# DIGITAL_IOs.net
KiCad netlist of a schematic drawn in Altium Designer
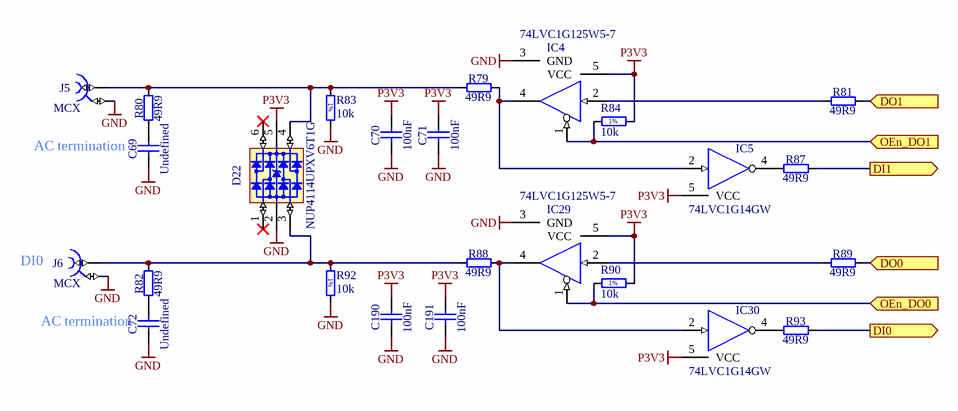
[diagram p0: DIGITAL_IOs.SchDoc]

(export (version "E")
  (design (tool "Eeschema 10.0.6"))
  (components
    (comp (ref "C69")
      (value "Undefined")
      (footprint "CAPC1608X90N")
      (description "Non-polarised capacitor")
      (fields (field (name "PART NUMBER") "CC0603_NO-VALUE") (field (name "AUTHOR") "CERN DEM MR"))
      (libsource (lib "Capacitors") (part "Capacitor - non polarized"))
    )
    (comp (ref "C70")
      (value "100nF")
      (footprint "CAPC1005X55N")
      (description "Non-polarised capacitor")
      (fields
        (field (name "PART NUMBER") "CC0402_100NF_16V_10%_X7R")
        (field (name "VOLTAGE") "16V")
        (field (name "AUTHOR") "CERN DEM JLC")
      )
      (libsource (lib "Capacitors") (part "Capacitor - non polarized"))
    )
    (comp (ref "C71")
      (value "100nF")
      (footprint "CAPC1005X55N")
      (description "Non-polarised capacitor")
      (fields
        (field (name "PART NUMBER") "CC0402_100NF_16V_10%_X7R")
        (field (name "VOLTAGE") "16V")
        (field (name "AUTHOR") "CERN DEM JLC")
      )
      (libsource (lib "Capacitors") (part "Capacitor - non polarized"))
    )
    (comp (ref "C72")
      (value "Undefined")
      (footprint "CAPC1608X90N")
      (description "Non-polarised capacitor")
      (fields (field (name "PART NUMBER") "CC0603_NO-VALUE") (field (name "AUTHOR") "CERN DEM MR"))
      (libsource (lib "Capacitors") (part "Capacitor - non polarized"))
    )
    (comp (ref "C190")
      (value "100nF")
      (footprint "CAPC1005X55N")
      (description "Non-polarised capacitor")
      (fields
        (field (name "PART NUMBER") "CC0402_100NF_16V_10%_X7R")
        (field (name "VOLTAGE") "16V")
        (field (name "AUTHOR") "CERN DEM JLC")
      )
      (libsource (lib "Capacitors") (part "Capacitor - non polarized"))
    )
    (comp (ref "C191")
      (value "100nF")
      (footprint "CAPC1005X55N")
      (description "Non-polarised capacitor")
      (fields
        (field (name "PART NUMBER") "CC0402_100NF_16V_10%_X7R")
        (field (name "VOLTAGE") "16V")
        (field (name "AUTHOR") "CERN DEM JLC")
      )
      (libsource (lib "Capacitors") (part "Capacitor - non polarized"))
    )
    (comp (ref "D22")
      (value "NUP4114UPXV6T1G")
      (footprint "SOTFL50P160X60-6N")
      (fields
        (field (name "VOLTAGE") "5.5V")
        (field (name "MANUFACTURER") "ON SEMICONDUCTOR")
        (field (name "AUTHOR") "CERN DEM JLC")
      )
      (libsource (lib "ICs And Semiconductors") (part "NUP4114"))
    )
    (comp (ref "IC4")
      (value "74LVC1G125W5-7")
      (footprint "SOT95P280X145-5N")
      (description "Single Bus Buffer Gate With 3-State Output")
      (fields (field (name "MANUFACTURER") "DIODES") (field (name "AUTHOR") "GK"))
      (libsource (lib "ICS-logic") (part "74LVC1G125W5-7"))
    )
    (comp (ref "IC5")
      (value "74LVC1G14GW")
      (footprint "SOT65P212X110-5N")
      (description "Single Schmitt-Trigger Inverter")
      (fields (field (name "MANUFACTURER") "NXP SEMICONDUCTORS") (field (name "AUTHOR") "CERN DEM JLC"))
      (libsource (lib "ICs And Semiconductors") (part "741G14"))
    )
    (comp (ref "IC29")
      (value "74LVC1G125W5-7")
      (footprint "SOT95P280X145-5N")
      (description "Single Bus Buffer Gate With 3-State Output")
      (fields (field (name "MANUFACTURER") "DIODES") (field (name "AUTHOR") "GK"))
      (libsource (lib "ICS-logic") (part "74LVC1G125W5-7"))
    )
    (comp (ref "IC30")
      (value "74LVC1G14GW")
      (footprint "SOT65P212X110-5N")
      (description "Single Schmitt-Trigger Inverter")
      (fields (field (name "MANUFACTURER") "NXP SEMICONDUCTORS") (field (name "AUTHOR") "CERN DEM JLC"))
      (libsource (lib "ICs And Semiconductors") (part "741G14"))
    )
    (comp (ref "J5")
      (value "MCX")
      (footprint "AMPHENOL_919-383J-51A")
      (fields
        (field (name "PART NUMBER") "AMPHENOL_919-383J-51A")
        (field (name "MANUFACTURER") "AMPHENOL")
        (field (name "MANUFACTURER PART NUMBER") "919-383J-51A")
        (field (name "AUTHOR") "CERN DEM BC")
      )
      (libsource (lib "Connectors") (part "Coax_1Female_1Shield"))
    )
    (comp (ref "J6")
      (value "MCX")
      (footprint "AMPHENOL_919-383J-51A")
      (fields
        (field (name "PART NUMBER") "AMPHENOL_919-383J-51A")
        (field (name "MANUFACTURER") "AMPHENOL")
        (field (name "MANUFACTURER PART NUMBER") "919-383J-51A")
        (field (name "AUTHOR") "CERN DEM BC")
      )
      (libsource (lib "Connectors") (part "Coax_1Female_1Shield"))
    )
    (comp (ref "R79")
      (value "49R9")
      (footprint "RESC1005X40N")
      (description "Resistor - 1%")
      (fields
        (field (name "PART NUMBER") "R0402_49R9_1%_0.0625W_100PPM")
        (field (name "POWER") "0.0625W")
        (field (name "AUTHOR") "CERN DEM JLC")
      )
      (libsource (lib "Resistors") (part "Resistor - 1%"))
    )
    (comp (ref "R80")
      (value "49R9")
      (footprint "RESC1005X40N")
      (description "Resistor - 1%")
      (fields
        (field (name "PART NUMBER") "R0402_49R9_1%_0.0625W_100PPM")
        (field (name "POWER") "0.0625W")
        (field (name "AUTHOR") "CERN DEM JLC")
      )
      (libsource (lib "Resistors") (part "Resistor - 1%"))
    )
    (comp (ref "R81")
      (value "49R9")
      (footprint "RESC1005X40N")
      (description "Resistor - 1%")
      (fields
        (field (name "PART NUMBER") "R0402_49R9_1%_0.0625W_100PPM")
        (field (name "POWER") "0.0625W")
        (field (name "AUTHOR") "CERN DEM JLC")
      )
      (libsource (lib "Resistors") (part "Resistor - 1%"))
    )
    (comp (ref "R82")
      (value "49R9")
      (footprint "RESC1005X40N")
      (description "Resistor - 1%")
      (fields
        (field (name "PART NUMBER") "R0402_49R9_1%_0.0625W_100PPM")
        (field (name "POWER") "0.0625W")
        (field (name "AUTHOR") "CERN DEM JLC")
      )
      (libsource (lib "Resistors") (part "Resistor - 1%"))
    )
    (comp (ref "R83")
      (value "10k")
      (footprint "RESC1005X40N")
      (description "Resistor - 1%")
      (fields
        (field (name "PART NUMBER") "R0402_10K_1%_0.0625W_100PPM")
        (field (name "POWER") "0.0625W")
        (field (name "AUTHOR") "CERN DEM JLC")
      )
      (libsource (lib "Resistors") (part "Resistor - 1%"))
    )
    (comp (ref "R84")
      (value "10k")
      (footprint "RESC1005X40N")
      (description "Resistor - 1%")
      (fields
        (field (name "PART NUMBER") "R0402_10K_1%_0.0625W_100PPM")
        (field (name "POWER") "0.0625W")
        (field (name "AUTHOR") "CERN DEM JLC")
      )
      (libsource (lib "Resistors") (part "Resistor - 1%"))
    )
    (comp (ref "R87")
      (value "49R9")
      (footprint "RESC1005X40N")
      (description "Resistor - 1%")
      (fields
        (field (name "PART NUMBER") "R0402_49R9_1%_0.0625W_100PPM")
        (field (name "POWER") "0.0625W")
        (field (name "AUTHOR") "CERN DEM JLC")
      )
      (libsource (lib "Resistors") (part "Resistor - 1%"))
    )
    (comp (ref "R88")
      (value "49R9")
      (footprint "RESC1005X40N")
      (description "Resistor - 1%")
      (fields
        (field (name "PART NUMBER") "R0402_49R9_1%_0.0625W_100PPM")
        (field (name "POWER") "0.0625W")
        (field (name "AUTHOR") "CERN DEM JLC")
      )
      (libsource (lib "Resistors") (part "Resistor - 1%"))
    )
    (comp (ref "R89")
      (value "49R9")
      (footprint "RESC1005X40N")
      (description "Resistor - 1%")
      (fields
        (field (name "PART NUMBER") "R0402_49R9_1%_0.0625W_100PPM")
        (field (name "POWER") "0.0625W")
        (field (name "AUTHOR") "CERN DEM JLC")
      )
      (libsource (lib "Resistors") (part "Resistor - 1%"))
    )
    (comp (ref "R90")
      (value "10k")
      (footprint "RESC1005X40N")
      (description "Resistor - 1%")
      (fields
        (field (name "PART NUMBER") "R0402_10K_1%_0.0625W_100PPM")
        (field (name "POWER") "0.0625W")
        (field (name "AUTHOR") "CERN DEM JLC")
      )
      (libsource (lib "Resistors") (part "Resistor - 1%"))
    )
    (comp (ref "R92")
      (value "10k")
      (footprint "RESC1005X40N")
      (description "Resistor - 1%")
      (fields
        (field (name "PART NUMBER") "R0402_10K_1%_0.0625W_100PPM")
        (field (name "POWER") "0.0625W")
        (field (name "AUTHOR") "CERN DEM JLC")
      )
      (libsource (lib "Resistors") (part "Resistor - 1%"))
    )
    (comp (ref "R93")
      (value "49R9")
      (footprint "RESC1005X40N")
      (description "Resistor - 1%")
      (fields
        (field (name "PART NUMBER") "R0402_49R9_1%_0.0625W_100PPM")
        (field (name "POWER") "0.0625W")
        (field (name "AUTHOR") "CERN DEM JLC")
      )
      (libsource (lib "Resistors") (part "Resistor - 1%"))
    )
  )
  (nets
    (net (code "1") (name "/DI0") (class "Default")
      (node (ref "R93") (pin "2") (pinfunction "2_2") (pintype "passive"))
    )
    (net (code "2") (name "/DI1") (class "Default")
      (node (ref "R87") (pin "2") (pinfunction "2_2") (pintype "passive"))
    )
    (net (code "3") (name "/DO0") (class "Default")
      (node (ref "R89") (pin "2") (pinfunction "2_2") (pintype "passive"))
    )
    (net (code "4") (name "/DO1") (class "Default")
      (node (ref "R81") (pin "2") (pinfunction "2_2") (pintype "passive"))
    )
    (net (code "5") (name "/OEn_DO0") (class "Default")
      (node (ref "IC29") (pin "1") (pinfunction "~{G}_1") (pintype "input"))
      (node (ref "R90") (pin "1") (pinfunction "1_1") (pintype "passive"))
    )
    (net (code "6") (name "/OEn_DO1") (class "Default")
      (node (ref "IC4") (pin "1") (pinfunction "~{G}_1") (pintype "input"))
      (node (ref "R84") (pin "1") (pinfunction "1_1") (pintype "passive"))
    )
    (net (code "7") (name "GND") (class "Default")
      (node (ref "C190") (pin "1") (pinfunction "1_1") (pintype "passive"))
      (node (ref "C191") (pin "1") (pinfunction "1_1") (pintype "passive"))
      (node (ref "C69") (pin "1") (pinfunction "1_1") (pintype "passive"))
      (node (ref "C70") (pin "1") (pinfunction "1_1") (pintype "passive"))
      (node (ref "C71") (pin "1") (pinfunction "1_1") (pintype "passive"))
      (node (ref "C72") (pin "1") (pinfunction "1_1") (pintype "passive"))
      (node (ref "D22") (pin "2") (pinfunction "GND_2") (pintype "power_in"))
      (node (ref "IC29") (pin "3") (pinfunction "GND_3") (pintype "power_in"))
      (node (ref "IC30") (pin "3") (pinfunction "GND_3") (pintype "power_in"))
      (node (ref "IC4") (pin "3") (pinfunction "GND_3") (pintype "power_in"))
      (node (ref "IC5") (pin "3") (pinfunction "GND_3") (pintype "power_in"))
      (node (ref "J5") (pin "2") (pinfunction "2_2") (pintype "bidirectional"))
      (node (ref "J6") (pin "2") (pinfunction "2_2") (pintype "bidirectional"))
      (node (ref "R83") (pin "2") (pinfunction "2_2") (pintype "passive"))
      (node (ref "R92") (pin "2") (pinfunction "2_2") (pintype "passive"))
    )
    (net (code "8") (name "Net-(C69-Pad2)") (class "Default")
      (node (ref "C69") (pin "2") (pinfunction "2_2") (pintype "passive"))
      (node (ref "R80") (pin "1") (pinfunction "1_1") (pintype "passive"))
    )
    (net (code "9") (name "Net-(C72-Pad2)") (class "Default")
      (node (ref "C72") (pin "2") (pinfunction "2_2") (pintype "passive"))
      (node (ref "R82") (pin "1") (pinfunction "1_1") (pintype "passive"))
    )
    (net (code "10") (name "Net-(D22-I{slash}O2)") (class "Default")
      (node (ref "D22") (pin "3") (pinfunction "I/O2_3") (pintype "bidirectional"))
      (node (ref "J6") (pin "1") (pinfunction "1_1") (pintype "bidirectional"))
      (node (ref "R82") (pin "2") (pinfunction "2_2") (pintype "passive"))
      (node (ref "R88") (pin "1") (pinfunction "1_1") (pintype "passive"))
      (node (ref "R92") (pin "1") (pinfunction "1_1") (pintype "passive"))
    )
    (net (code "11") (name "Net-(D22-I{slash}O3)") (class "Default")
      (node (ref "D22") (pin "4") (pinfunction "I/O3_4") (pintype "bidirectional"))
      (node (ref "J5") (pin "1") (pinfunction "1_1") (pintype "bidirectional"))
      (node (ref "R79") (pin "1") (pinfunction "1_1") (pintype "passive"))
      (node (ref "R80") (pin "2") (pinfunction "2_2") (pintype "passive"))
      (node (ref "R83") (pin "1") (pinfunction "1_1") (pintype "passive"))
    )
    (net (code "12") (name "Net-(IC4-IN)") (class "Default")
      (node (ref "IC4") (pin "2") (pinfunction "IN_2") (pintype "input"))
      (node (ref "R81") (pin "1") (pinfunction "1_1") (pintype "passive"))
    )
    (net (code "13") (name "Net-(IC4-OUT)") (class "Default")
      (node (ref "IC4") (pin "4") (pinfunction "OUT_4") (pintype "tri_state"))
      (node (ref "IC5") (pin "2") (pinfunction "IN_2") (pintype "input"))
      (node (ref "R79") (pin "2") (pinfunction "2_2") (pintype "passive"))
    )
    (net (code "14") (name "Net-(IC5-OUT)") (class "Default")
      (node (ref "IC5") (pin "4") (pinfunction "OUT_4") (pintype "open_collector"))
      (node (ref "R87") (pin "1") (pinfunction "1_1") (pintype "passive"))
    )
    (net (code "15") (name "Net-(IC29-IN)") (class "Default")
      (node (ref "IC29") (pin "2") (pinfunction "IN_2") (pintype "input"))
      (node (ref "R89") (pin "1") (pinfunction "1_1") (pintype "passive"))
    )
    (net (code "16") (name "Net-(IC29-OUT)") (class "Default")
      (node (ref "IC29") (pin "4") (pinfunction "OUT_4") (pintype "tri_state"))
      (node (ref "IC30") (pin "2") (pinfunction "IN_2") (pintype "input"))
      (node (ref "R88") (pin "2") (pinfunction "2_2") (pintype "passive"))
    )
    (net (code "17") (name "Net-(IC30-OUT)") (class "Default")
      (node (ref "IC30") (pin "4") (pinfunction "OUT_4") (pintype "open_collector"))
      (node (ref "R93") (pin "1") (pinfunction "1_1") (pintype "passive"))
    )
    (net (code "18") (name "P3V3") (class "Default")
      (node (ref "C190") (pin "2") (pinfunction "2_2") (pintype "passive"))
      (node (ref "C191") (pin "2") (pinfunction "2_2") (pintype "passive"))
      (node (ref "C70") (pin "2") (pinfunction "2_2") (pintype "passive"))
      (node (ref "C71") (pin "2") (pinfunction "2_2") (pintype "passive"))
      (node (ref "D22") (pin "5") (pinfunction "VBUS_5") (pintype "power_in"))
      (node (ref "IC29") (pin "5") (pinfunction "VCC_5") (pintype "power_in"))
      (node (ref "IC30") (pin "5") (pinfunction "VCC_5") (pintype "power_in"))
      (node (ref "IC4") (pin "5") (pinfunction "VCC_5") (pintype "power_in"))
      (node (ref "IC5") (pin "5") (pinfunction "VCC_5") (pintype "power_in"))
      (node (ref "R84") (pin "2") (pinfunction "2_2") (pintype "passive"))
      (node (ref "R90") (pin "2") (pinfunction "2_2") (pintype "passive"))
    )
    (net (code "19") (name "unconnected-(D22-I{slash}O1-Pad1)") (class "Default")
      (node (ref "D22") (pin "1") (pinfunction "I/O1_1") (pintype "bidirectional+no_connect"))
    )
    (net (code "20") (name "unconnected-(D22-I{slash}O4-Pad6)") (class "Default")
      (node (ref "D22") (pin "6") (pinfunction "I/O4_6") (pintype "bidirectional+no_connect"))
    )
  )
)
